# CH32F207_V307V-R3.net
KiCad netlist of a schematic drawn in Altium Designer
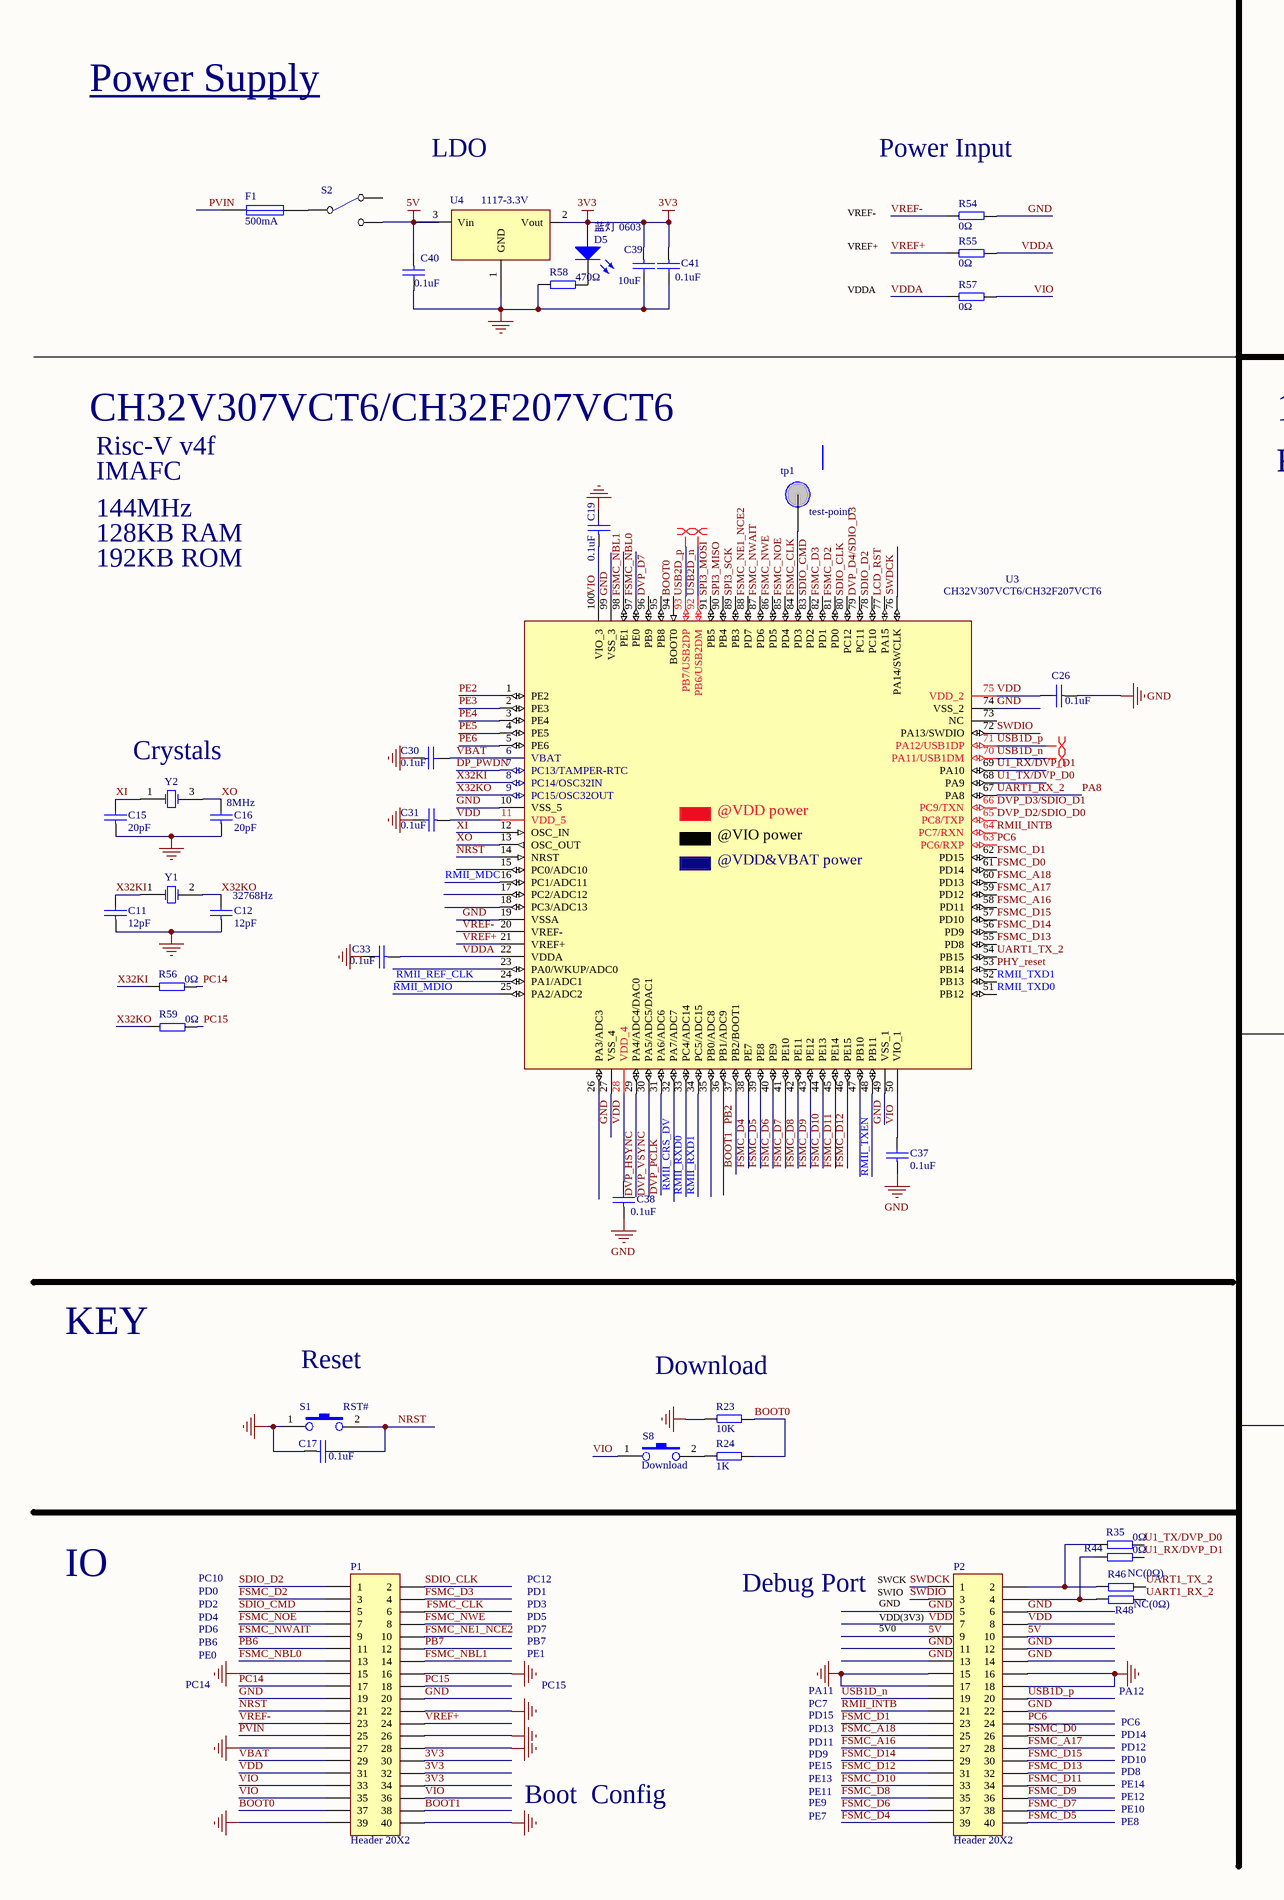
[diagram p0: CH32F207&V307V-R3.SchDoc, left]
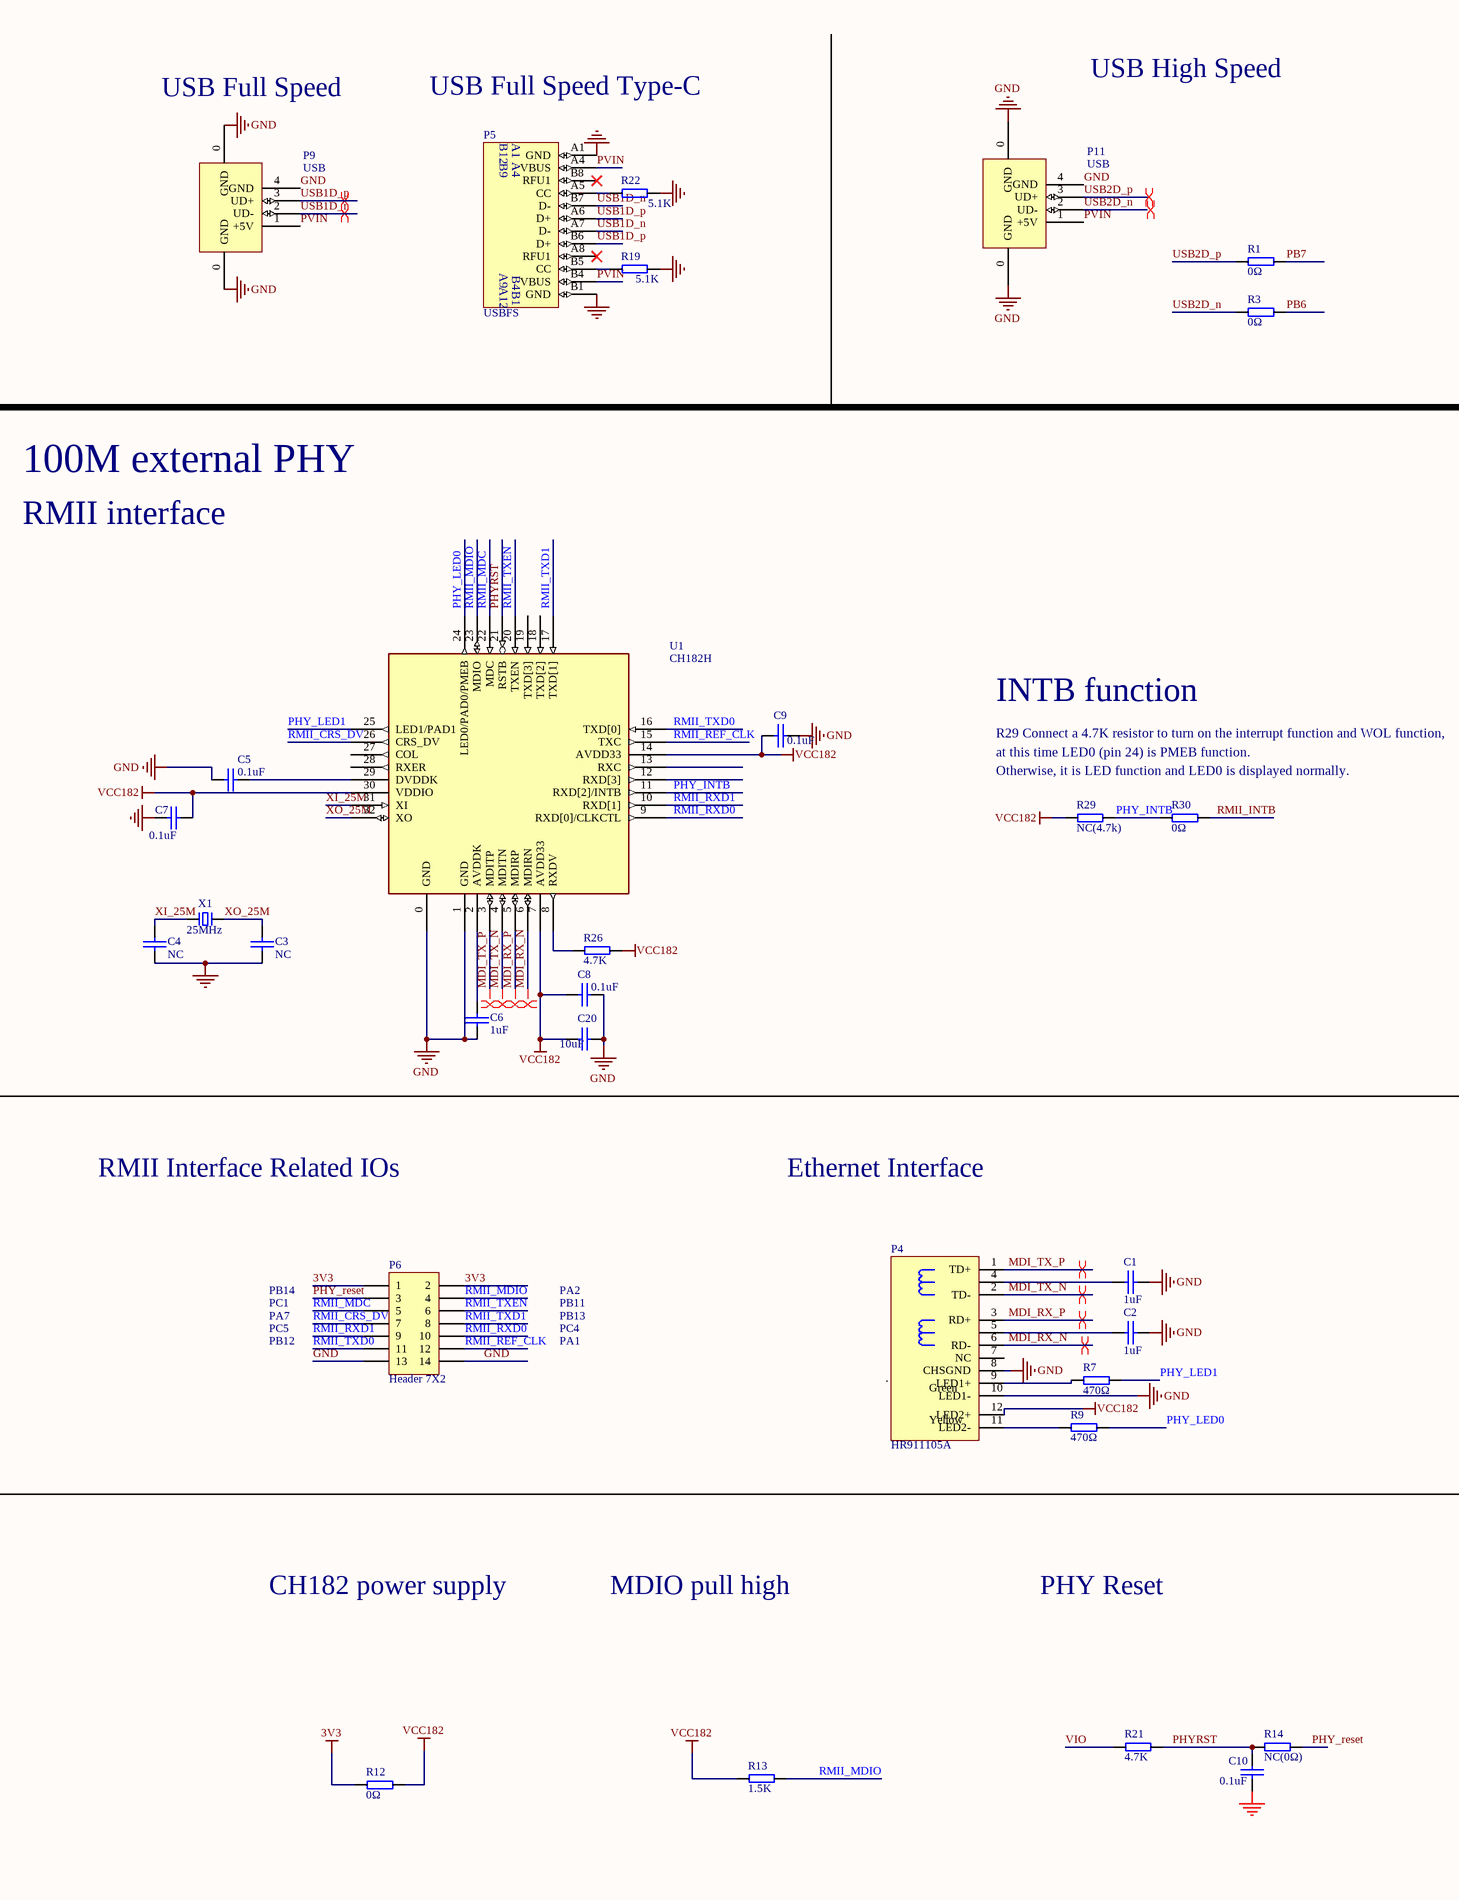
[diagram p1: CH32F207&V307V-R3.SchDoc, right]

(export (version "E")
  (design (tool "Eeschema 10.0.6"))
  (components
    (comp (ref "C1")
      (value "1uF")
      (footprint "0603_C")
      (description "Capacitor")
      (libsource (lib "wch_sch_others") (part "CAP"))
    )
    (comp (ref "C2")
      (value "1uF")
      (footprint "0603_C")
      (description "Capacitor")
      (libsource (lib "wch_sch_others") (part "CAP"))
    )
    (comp (ref "C3")
      (value "NC")
      (footprint "0603_C")
      (description "Capacitor")
      (libsource (lib "wch_sch_others") (part "CAP"))
    )
    (comp (ref "C4")
      (value "NC")
      (footprint "0603_C")
      (description "Capacitor")
      (libsource (lib "wch_sch_others") (part "CAP"))
    )
    (comp (ref "C5")
      (value "0.1uF")
      (footprint "0603_C")
      (description "Capacitor")
      (libsource (lib "wch_sch_others") (part "CAP"))
    )
    (comp (ref "C6")
      (value "1uF")
      (footprint "0603_C")
      (description "Capacitor")
      (libsource (lib "wch_sch_others") (part "CAP"))
    )
    (comp (ref "C7")
      (value "0.1uF")
      (footprint "0603_C")
      (description "Capacitor")
      (libsource (lib "wch_sch_others") (part "CAP"))
    )
    (comp (ref "C8")
      (value "0.1uF")
      (footprint "0603_C")
      (description "Capacitor")
      (libsource (lib "wch_sch_others") (part "CAP"))
    )
    (comp (ref "C9")
      (value "0.1uF")
      (footprint "0603_C")
      (description "Capacitor")
      (libsource (lib "wch_sch_others") (part "CAP"))
    )
    (comp (ref "C10")
      (value "0.1uF")
      (footprint "0603_C")
      (description "Capacitor")
      (libsource (lib "") (part "CAP_1"))
    )
    (comp (ref "C11")
      (value "12pF")
      (footprint "0603_C")
      (description "Capacitor")
      (libsource (lib "") (part "CAP_1"))
    )
    (comp (ref "C12")
      (value "12pF")
      (footprint "0603_C")
      (description "Capacitor")
      (libsource (lib "") (part "CAP_1"))
    )
    (comp (ref "C15")
      (value "20pF")
      (footprint "0603_C")
      (description "Capacitor")
      (libsource (lib "") (part "CAP_1"))
    )
    (comp (ref "C16")
      (value "20pF")
      (footprint "0603_C")
      (description "Capacitor")
      (libsource (lib "") (part "CAP_1"))
    )
    (comp (ref "C17")
      (value "0.1uF")
      (footprint "0603_C")
      (description "Capacitor")
      (libsource (lib "*") (part "CAP"))
    )
    (comp (ref "C19")
      (value "0.1uF")
      (footprint "0603_C")
      (description "Capacitor")
      (libsource (lib "") (part "CAP_1"))
    )
    (comp (ref "C20")
      (value "10uF")
      (footprint "0603_C")
      (description "Capacitor")
      (libsource (lib "wch_sch_others") (part "CAP"))
    )
    (comp (ref "C26")
      (value "0.1uF")
      (footprint "0603_C")
      (description "Capacitor")
      (libsource (lib "") (part "CAP_1"))
    )
    (comp (ref "C30")
      (value "0.1uF")
      (footprint "0603_C")
      (description "Capacitor")
      (libsource (lib "") (part "CAP_1"))
    )
    (comp (ref "C31")
      (value "0.1uF")
      (footprint "0603_C")
      (description "Capacitor")
      (libsource (lib "") (part "CAP_1"))
    )
    (comp (ref "C33")
      (value "0.1uF")
      (footprint "0603_C")
      (description "Capacitor")
      (libsource (lib "") (part "CAP_1"))
    )
    (comp (ref "C37")
      (value "0.1uF")
      (footprint "0603_C")
      (description "Capacitor")
      (libsource (lib "") (part "CAP_1"))
    )
    (comp (ref "C38")
      (value "0.1uF")
      (footprint "0603_C")
      (description "Capacitor")
      (libsource (lib "") (part "CAP_1"))
    )
    (comp (ref "C39")
      (value "10uF")
      (footprint "0603_C")
      (description "Capacitor")
      (libsource (lib "") (part "CAP_1"))
    )
    (comp (ref "C40")
      (value "0.1uF")
      (footprint "0603_C")
      (description "Capacitor")
      (libsource (lib "") (part "CAP_1"))
    )
    (comp (ref "C41")
      (value "0.1uF")
      (footprint "0603_C")
      (description "Capacitor")
      (libsource (lib "") (part "CAP_1"))
    )
    (comp (ref "D5")
      (value "蓝灯 0603")
      (footprint "0603_LED_S1")
      (description "发光二极管")
      (libsource (lib "Miscellaneous Devices LC") (part "0603 蓝灯"))
    )
    (comp (ref "F1")
      (value "500mA")
      (footprint "0805")
      (description "Fuse")
      (fields (field (name "PUBLISHER") "Altium Limited"))
      (libsource (lib "Miscellaneous Devices") (part "Fuse 1"))
    )
    (comp (ref "P1")
      (value "Header 20X2")
      (footprint "HDR2X20")
      (description "Header, 20-Pin, Dual row")
      (fields (field (name "PUBLISHER") "Altium Limited"))
      (libsource (lib "Miscellaneous Connectors") (part "Header 20X2"))
    )
    (comp (ref "P2")
      (value "Header 20X2")
      (footprint "HDR2X20")
      (description "Header, 20-Pin, Dual row")
      (fields (field (name "PUBLISHER") "Altium Limited"))
      (libsource (lib "Miscellaneous Connectors") (part "Header 20X2"))
    )
    (comp (ref "P4")
      (value "HR911105A")
      (footprint "HR911105A")
      (libsource (lib "wch_sch_others") (part "HR911105A_1"))
    )
    (comp (ref "P5")
      (value "USBFS")
      (footprint "TYPE-C-Receptacle-2.0")
      (libsource (lib "*") (part "TYPE-C1"))
    )
    (comp (ref "P6")
      (value "Header 7X2")
      (footprint "IDC14-2.54mm")
      (description "Header, 7-Pin, Dual row")
      (fields (field (name "PUBLISHER") "Altium Limited"))
      (libsource (lib "Miscellaneous Connectors") (part "Header 7X2"))
    )
    (comp (ref "P9")
      (value "USB")
      (footprint "USBAF")
      (description "USB Port")
      (libsource (lib "CHXXX") (part "USB"))
    )
    (comp (ref "P11")
      (value "USB")
      (footprint "USBAF")
      (description "USB Port")
      (libsource (lib "CHXXX") (part "USB"))
    )
    (comp (ref "R1") (value "0Ω") (footprint "0603") (libsource (lib "wch_sch_others") (part "RES")))
    (comp (ref "R3") (value "0Ω") (footprint "0603") (libsource (lib "wch_sch_others") (part "RES")))
    (comp (ref "R7") (value "470Ω") (footprint "0603") (libsource (lib "wch_sch_others") (part "RES")))
    (comp (ref "R9") (value "470Ω") (footprint "0603") (libsource (lib "wch_sch_others") (part "RES")))
    (comp (ref "R12") (value "0Ω") (footprint "0603") (libsource (lib "wch_sch_others") (part "RES")))
    (comp (ref "R13") (value "1.5K") (footprint "0603") (libsource (lib "wch_sch_others") (part "RES")))
    (comp (ref "R14") (value "NC(0Ω)") (footprint "0603") (libsource (lib "wch_sch_others") (part "RES")))
    (comp (ref "R19") (value "5.1K") (footprint "0603") (libsource (lib "wch_sch_others") (part "RES")))
    (comp (ref "R21") (value "4.7K") (footprint "0603") (libsource (lib "wch_sch_others") (part "RES")))
    (comp (ref "R22") (value "5.1K") (footprint "0603") (libsource (lib "wch_sch_others") (part "RES")))
    (comp (ref "R23") (value "10K") (footprint "0603") (libsource (lib "wch_sch_others") (part "RES")))
    (comp (ref "R24") (value "1K") (footprint "0603") (libsource (lib "wch_sch_others") (part "RES")))
    (comp (ref "R26") (value "4.7K") (footprint "0603") (libsource (lib "wch_sch_others") (part "RES")))
    (comp (ref "R29") (value "NC(4.7k)") (footprint "0603") (libsource (lib "wch_sch_others") (part "RES")))
    (comp (ref "R30") (value "0Ω") (footprint "0603") (libsource (lib "wch_sch_others") (part "RES")))
    (comp (ref "R35") (value "0Ω") (footprint "0603") (libsource (lib "wch_sch_others") (part "RES")))
    (comp (ref "R44") (value "0Ω") (footprint "0603") (libsource (lib "wch_sch_others") (part "RES")))
    (comp (ref "R46") (value "NC(0Ω)") (footprint "0603") (libsource (lib "wch_sch_others") (part "RES")))
    (comp (ref "R48") (value "NC(0Ω)") (footprint "0603") (libsource (lib "wch_sch_others") (part "RES")))
    (comp (ref "R54") (value "0Ω") (footprint "0603") (libsource (lib "wch_sch_others") (part "RES")))
    (comp (ref "R55") (value "0Ω") (footprint "0603") (libsource (lib "wch_sch_others") (part "RES")))
    (comp (ref "R56") (value "0Ω") (footprint "0603") (libsource (lib "wch_sch_others") (part "RES")))
    (comp (ref "R57") (value "0Ω") (footprint "0603") (libsource (lib "wch_sch_others") (part "RES")))
    (comp (ref "R58") (value "470Ω") (footprint "0603") (libsource (lib "wch_sch_others") (part "RES")))
    (comp (ref "R59") (value "0Ω") (footprint "0603") (libsource (lib "wch_sch_others") (part "RES")))
    (comp (ref "S1")
      (value "RST#")
      (footprint "SMD_6.1x3.65x2.5mm-KEY")
      (libsource (lib "wch_sch_others") (part "KEY1"))
    )
    (comp (ref "S2")
      (value "SW SPDT")
      (footprint "Horizontal Slide Switch_8.7x4.4mm-2D")
      (libsource (lib "*") (part "SW SPDT"))
    )
    (comp (ref "S8")
      (value "Download")
      (footprint "SMD_6.1x3.65x2.5mm-KEY")
      (libsource (lib "wch_sch_others") (part "KEY1"))
    )
    (comp (ref "tp1")
      (value "test-point")
      (footprint "POINT")
      (description "测试点")
      (libsource (lib "五向开关") (part "test-point"))
    )
    (comp (ref "U1")
      (value "CH182H")
      (footprint "QFN32_5X5")
      (description "MII/RMII 10/100M Ethernet PHY (Transceiver) with auto MDIX")
      (libsource (lib "CHXXX") (part "CH182H"))
    )
    (comp (ref "U3")
      (value "CH32V307VCT6/CH32F207VCT6")
      (footprint "LQFP100")
      (description "RISC-V FPU HD-MCU, 144MHz, USB_480M, USB OTG, 1000M Ethernet MAC, 2*CAN, FSMC+DVP")
      (libsource (lib "CHXXX") (part "CH32V307V"))
    )
    (comp (ref "U4")
      (value "1117-3.3V")
      (footprint "SOT-223")
      (libsource (lib "wch_sch_others") (part "1117-3.3V"))
    )
    (comp (ref "X1")
      (value "25MHz")
      (footprint "SMD-3225_4P")
      (description "2脚无源脚晶振")
      (libsource (lib "10.1 - 保险丝-晶振") (part "XTAL-2P"))
    )
    (comp (ref "Y1")
      (value "32768Hz")
      (footprint "FC-135")
      (description "Crystal Oscillator")
      (fields (field (name "PUBLISHER") "Altium Limited"))
      (libsource (lib "") (part "XTAL_1"))
    )
    (comp (ref "Y2")
      (value "8MHz")
      (footprint "SMD-3225_4P")
      (description "Crystal Oscillator")
      (fields (field (name "PUBLISHER") "Altium Limited"))
      (libsource (lib "*") (part "XTAL"))
    )
  )
  (nets
    (net (code "2") (name "/BOOT0") (class "Default")
      (node (ref "P1") (pin "37") (pinfunction "37_37") (pintype "passive"))
      (node (ref "R23") (pin "1") (pintype "passive"))
      (node (ref "R24") (pin "1") (pintype "passive"))
      (node (ref "U3") (pin "94") (pinfunction "BOOT0_94") (pintype "input"))
    )
    (net (code "3") (name "/BOOT1") (class "Default")
      (node (ref "P1") (pin "38") (pinfunction "38_38") (pintype "passive"))
      (node (ref "U3") (pin "37") (pinfunction "PB2/BOOT1_37") (pintype "bidirectional"))
    )
    (net (code "4") (name "/DP_PWDN") (class "Default")
      (node (ref "U3") (pin "7") (pinfunction "PC13/TAMPER-RTC_7") (pintype "bidirectional"))
    )
    (net (code "5") (name "/DVP_D2{slash}SDIO_D0") (class "Default")
      (node (ref "U3") (pin "65") (pinfunction "PC8/TXP_65") (pintype "bidirectional"))
    )
    (net (code "6") (name "/DVP_D3{slash}SDIO_D1") (class "Default")
      (node (ref "U3") (pin "66") (pinfunction "PC9/TXN_66") (pintype "bidirectional"))
    )
    (net (code "7") (name "/DVP_D4{slash}SDIO_D3") (class "Default")
      (node (ref "U3") (pin "79") (pinfunction "PC11_79") (pintype "bidirectional"))
    )
    (net (code "8") (name "/DVP_D7") (class "Default")
      (node (ref "U3") (pin "96") (pinfunction "PB9_96") (pintype "bidirectional"))
    )
    (net (code "9") (name "/DVP_HSYNC") (class "Default")
      (node (ref "U3") (pin "29") (pinfunction "PA4/ADC4/DAC0_29") (pintype "bidirectional"))
    )
    (net (code "10") (name "/DVP_PCLK") (class "Default")
      (node (ref "U3") (pin "31") (pinfunction "PA6/ADC6_31") (pintype "bidirectional"))
    )
    (net (code "11") (name "/DVP_VSYNC") (class "Default")
      (node (ref "U3") (pin "30") (pinfunction "PA5/ADC5/DAC1_30") (pintype "bidirectional"))
    )
    (net (code "12") (name "/FSMC_A16") (class "Default")
      (node (ref "P2") (pin "27") (pinfunction "27_27") (pintype "passive"))
      (node (ref "U3") (pin "58") (pinfunction "PD11_58") (pintype "bidirectional"))
    )
    (net (code "13") (name "/FSMC_A17") (class "Default")
      (node (ref "P2") (pin "28") (pinfunction "28_28") (pintype "passive"))
      (node (ref "U3") (pin "59") (pinfunction "PD12_59") (pintype "bidirectional"))
    )
    (net (code "14") (name "/FSMC_A18") (class "Default")
      (node (ref "P2") (pin "25") (pinfunction "25_25") (pintype "passive"))
      (node (ref "U3") (pin "60") (pinfunction "PD13_60") (pintype "bidirectional"))
    )
    (net (code "15") (name "/FSMC_CLK") (class "Default")
      (node (ref "P1") (pin "6") (pinfunction "6_6") (pintype "passive"))
      (node (ref "U3") (pin "84") (pinfunction "PD3_84") (pintype "bidirectional"))
      (node (ref "tp1") (pin "1") (pinfunction "point_1") (pintype "passive"))
    )
    (net (code "16") (name "/FSMC_D0") (class "Default")
      (node (ref "P2") (pin "26") (pinfunction "26_26") (pintype "passive"))
      (node (ref "U3") (pin "61") (pinfunction "PD14_61") (pintype "bidirectional"))
    )
    (net (code "17") (name "/FSMC_D1") (class "Default")
      (node (ref "P2") (pin "23") (pinfunction "23_23") (pintype "passive"))
      (node (ref "U3") (pin "62") (pinfunction "PD15_62") (pintype "bidirectional"))
    )
    (net (code "18") (name "/FSMC_D2") (class "Default")
      (node (ref "P1") (pin "3") (pinfunction "3_3") (pintype "passive"))
      (node (ref "U3") (pin "81") (pinfunction "PD0_81") (pintype "bidirectional"))
    )
    (net (code "19") (name "/FSMC_D3") (class "Default")
      (node (ref "P1") (pin "4") (pinfunction "4_4") (pintype "passive"))
      (node (ref "U3") (pin "82") (pinfunction "PD1_82") (pintype "bidirectional"))
    )
    (net (code "20") (name "/FSMC_D4") (class "Default")
      (node (ref "P2") (pin "39") (pinfunction "39_39") (pintype "passive"))
      (node (ref "U3") (pin "38") (pinfunction "PE7_38") (pintype "bidirectional"))
    )
    (net (code "21") (name "/FSMC_D5") (class "Default")
      (node (ref "P2") (pin "40") (pinfunction "40_40") (pintype "passive"))
      (node (ref "U3") (pin "39") (pinfunction "PE8_39") (pintype "bidirectional"))
    )
    (net (code "22") (name "/FSMC_D6") (class "Default")
      (node (ref "P2") (pin "37") (pinfunction "37_37") (pintype "passive"))
      (node (ref "U3") (pin "40") (pinfunction "PE9_40") (pintype "bidirectional"))
    )
    (net (code "23") (name "/FSMC_D7") (class "Default")
      (node (ref "P2") (pin "38") (pinfunction "38_38") (pintype "passive"))
      (node (ref "U3") (pin "41") (pinfunction "PE10_41") (pintype "bidirectional"))
    )
    (net (code "24") (name "/FSMC_D8") (class "Default")
      (node (ref "P2") (pin "35") (pinfunction "35_35") (pintype "passive"))
      (node (ref "U3") (pin "42") (pinfunction "PE11_42") (pintype "bidirectional"))
    )
    (net (code "25") (name "/FSMC_D9") (class "Default")
      (node (ref "P2") (pin "36") (pinfunction "36_36") (pintype "passive"))
      (node (ref "U3") (pin "43") (pinfunction "PE12_43") (pintype "bidirectional"))
    )
    (net (code "26") (name "/FSMC_D10") (class "Default")
      (node (ref "P2") (pin "33") (pinfunction "33_33") (pintype "passive"))
      (node (ref "U3") (pin "44") (pinfunction "PE13_44") (pintype "bidirectional"))
    )
    (net (code "27") (name "/FSMC_D11") (class "Default")
      (node (ref "P2") (pin "34") (pinfunction "34_34") (pintype "passive"))
      (node (ref "U3") (pin "45") (pinfunction "PE14_45") (pintype "bidirectional"))
    )
    (net (code "28") (name "/FSMC_D12") (class "Default")
      (node (ref "P2") (pin "31") (pinfunction "31_31") (pintype "passive"))
      (node (ref "U3") (pin "46") (pinfunction "PE15_46") (pintype "bidirectional"))
    )
    (net (code "29") (name "/FSMC_D13") (class "Default")
      (node (ref "P2") (pin "32") (pinfunction "32_32") (pintype "passive"))
      (node (ref "U3") (pin "55") (pinfunction "PD8_55") (pintype "bidirectional"))
    )
    (net (code "30") (name "/FSMC_D14") (class "Default")
      (node (ref "P2") (pin "29") (pinfunction "29_29") (pintype "passive"))
      (node (ref "U3") (pin "56") (pinfunction "PD9_56") (pintype "bidirectional"))
    )
    (net (code "31") (name "/FSMC_D15") (class "Default")
      (node (ref "P2") (pin "30") (pinfunction "30_30") (pintype "passive"))
      (node (ref "U3") (pin "57") (pinfunction "PD10_57") (pintype "bidirectional"))
    )
    (net (code "32") (name "/FSMC_NBL0") (class "Default")
      (node (ref "P1") (pin "13") (pinfunction "13_13") (pintype "passive"))
      (node (ref "U3") (pin "97") (pinfunction "PE0_97") (pintype "bidirectional"))
    )
    (net (code "33") (name "/FSMC_NBL1") (class "Default")
      (node (ref "P1") (pin "14") (pinfunction "14_14") (pintype "passive"))
      (node (ref "U3") (pin "98") (pinfunction "PE1_98") (pintype "bidirectional"))
    )
    (net (code "34") (name "/FSMC_NE1_NCE2") (class "Default")
      (node (ref "P1") (pin "10") (pinfunction "10_10") (pintype "passive"))
      (node (ref "U3") (pin "88") (pinfunction "PD7_88") (pintype "bidirectional"))
    )
    (net (code "35") (name "/FSMC_NOE") (class "Default")
      (node (ref "P1") (pin "7") (pinfunction "7_7") (pintype "passive"))
      (node (ref "U3") (pin "85") (pinfunction "PD4_85") (pintype "bidirectional"))
    )
    (net (code "36") (name "/FSMC_NWAIT") (class "Default")
      (node (ref "P1") (pin "9") (pinfunction "9_9") (pintype "passive"))
      (node (ref "U3") (pin "87") (pinfunction "PD6_87") (pintype "bidirectional"))
    )
    (net (code "37") (name "/FSMC_NWE") (class "Default")
      (node (ref "P1") (pin "8") (pinfunction "8_8") (pintype "passive"))
      (node (ref "U3") (pin "86") (pinfunction "PD5_86") (pintype "bidirectional"))
    )
    (net (code "38") (name "/LCD_RST") (class "Default")
      (node (ref "U3") (pin "77") (pinfunction "PA15_77") (pintype "bidirectional"))
    )
    (net (code "39") (name "/MDI_RX_N") (class "Default")
      (node (ref "P4") (pin "6") (pinfunction "RD-_6") (pintype "passive"))
      (node (ref "U1") (pin "6") (pinfunction "MDIRN_6") (pintype "bidirectional"))
    )
    (net (code "40") (name "/MDI_RX_P") (class "Default")
      (node (ref "P4") (pin "3") (pinfunction "RD+_3") (pintype "passive"))
      (node (ref "U1") (pin "5") (pinfunction "MDIRP_5") (pintype "bidirectional"))
    )
    (net (code "41") (name "/MDI_TX_N") (class "Default")
      (node (ref "P4") (pin "2") (pinfunction "TD-_2") (pintype "passive"))
      (node (ref "U1") (pin "4") (pinfunction "MDITN_4") (pintype "bidirectional"))
    )
    (net (code "42") (name "/MDI_TX_P") (class "Default")
      (node (ref "P4") (pin "1") (pinfunction "TD+_1") (pintype "passive"))
      (node (ref "U1") (pin "3") (pinfunction "MDITP_3") (pintype "bidirectional"))
    )
    (net (code "43") (name "/NRST") (class "Default")
      (node (ref "C17") (pin "2") (pinfunction "2_2") (pintype "passive"))
      (node (ref "P1") (pin "21") (pinfunction "21_21") (pintype "passive"))
      (node (ref "S1") (pin "2") (pinfunction "2_2") (pintype "passive"))
      (node (ref "U3") (pin "14") (pinfunction "NRST_14") (pintype "input"))
    )
    (net (code "44") (name "/PA8") (class "Default")
      (node (ref "R48") (pin "2") (pintype "passive"))
      (node (ref "U3") (pin "67") (pinfunction "PA8_67") (pintype "bidirectional"))
    )
    (net (code "45") (name "/PB6") (class "Default")
      (node (ref "P1") (pin "11") (pinfunction "11_11") (pintype "passive"))
      (node (ref "R3") (pin "2") (pintype "passive"))
    )
    (net (code "46") (name "/PB7") (class "Default")
      (node (ref "P1") (pin "12") (pinfunction "12_12") (pintype "passive"))
      (node (ref "R1") (pin "2") (pintype "passive"))
    )
    (net (code "47") (name "/PC6") (class "Default")
      (node (ref "P2") (pin "24") (pinfunction "24_24") (pintype "passive"))
      (node (ref "U3") (pin "63") (pinfunction "PC6/RXP_63") (pintype "bidirectional"))
    )
    (net (code "48") (name "/PC14") (class "Default")
      (node (ref "P1") (pin "17") (pinfunction "17_17") (pintype "passive"))
      (node (ref "R56") (pin "2") (pintype "passive"))
    )
    (net (code "49") (name "/PC15") (class "Default")
      (node (ref "P1") (pin "18") (pinfunction "18_18") (pintype "passive"))
      (node (ref "R59") (pin "2") (pintype "passive"))
    )
    (net (code "50") (name "/PE2") (class "Default")
      (node (ref "U3") (pin "1") (pinfunction "PE2_1") (pintype "bidirectional"))
    )
    (net (code "51") (name "/PE3") (class "Default")
      (node (ref "U3") (pin "2") (pinfunction "PE3_2") (pintype "bidirectional"))
    )
    (net (code "52") (name "/PE4") (class "Default")
      (node (ref "U3") (pin "3") (pinfunction "PE4_3") (pintype "bidirectional"))
    )
    (net (code "53") (name "/PE5") (class "Default")
      (node (ref "U3") (pin "4") (pinfunction "PE5_4") (pintype "bidirectional"))
    )
    (net (code "54") (name "/PE6") (class "Default")
      (node (ref "U3") (pin "5") (pinfunction "PE6_5") (pintype "bidirectional"))
    )
    (net (code "55") (name "/PHYRST") (class "Default")
      (node (ref "C10") (pin "2") (pinfunction "2_2") (pintype "passive"))
      (node (ref "R14") (pin "1") (pintype "passive"))
      (node (ref "R21") (pin "1") (pintype "passive"))
      (node (ref "U1") (pin "21") (pinfunction "RSTB_21") (pintype "input"))
    )
    (net (code "56") (name "/PHY_INTB") (class "Default")
      (node (ref "R29") (pin "1") (pintype "passive"))
      (node (ref "R30") (pin "1") (pintype "passive"))
      (node (ref "U1") (pin "11") (pinfunction "RXD[2]/INTB_11") (pintype "output"))
    )
    (net (code "57") (name "/PHY_LED0") (class "Default")
      (node (ref "R9") (pin "2") (pintype "passive"))
      (node (ref "U1") (pin "24") (pinfunction "LED0/PAD0/PMEB_24") (pintype "output"))
    )
    (net (code "58") (name "/PHY_LED1") (class "Default")
      (node (ref "R7") (pin "2") (pintype "passive"))
      (node (ref "U1") (pin "25") (pinfunction "LED1/PAD1_25") (pintype "output"))
    )
    (net (code "59") (name "/PHY_reset") (class "Default")
      (node (ref "P6") (pin "3") (pinfunction "3_3") (pintype "passive"))
      (node (ref "R14") (pin "2") (pintype "passive"))
      (node (ref "U3") (pin "53") (pinfunction "PB14_53") (pintype "bidirectional"))
    )
    (net (code "60") (name "/PVIN") (class "Default")
      (node (ref "F1") (pin "1") (pinfunction "1_1") (pintype "passive"))
      (node (ref "P1") (pin "25") (pinfunction "25_25") (pintype "passive"))
      (node (ref "P11") (pin "1") (pinfunction "+5V_1") (pintype "power_in"))
      (node (ref "P5") (pin "A4") (pinfunction "VBUS_A4") (pintype "bidirectional"))
      (node (ref "P5") (pin "B4") (pinfunction "VBUS_B4") (pintype "bidirectional"))
      (node (ref "P9") (pin "1") (pinfunction "+5V_1") (pintype "power_in"))
    )
    (net (code "61") (name "/RMII_CRS_DV") (class "Default")
      (node (ref "P6") (pin "7") (pinfunction "7_7") (pintype "passive"))
      (node (ref "U1") (pin "26") (pinfunction "CRS_DV_26") (pintype "output"))
      (node (ref "U3") (pin "32") (pinfunction "PA7/ADC7_32") (pintype "bidirectional"))
    )
    (net (code "62") (name "/RMII_INTB") (class "Default")
      (node (ref "P2") (pin "21") (pinfunction "21_21") (pintype "passive"))
      (node (ref "R30") (pin "2") (pintype "passive"))
      (node (ref "U3") (pin "64") (pinfunction "PC7/RXN_64") (pintype "bidirectional"))
    )
    (net (code "63") (name "/RMII_MDC") (class "Default")
      (node (ref "P6") (pin "5") (pinfunction "5_5") (pintype "passive"))
      (node (ref "U1") (pin "22") (pinfunction "MDC_22") (pintype "input"))
      (node (ref "U3") (pin "16") (pinfunction "PC1/ADC11_16") (pintype "bidirectional"))
    )
    (net (code "64") (name "/RMII_MDIO") (class "Default")
      (node (ref "P6") (pin "4") (pinfunction "4_4") (pintype "passive"))
      (node (ref "R13") (pin "2") (pintype "passive"))
      (node (ref "U1") (pin "23") (pinfunction "MDIO_23") (pintype "bidirectional"))
      (node (ref "U3") (pin "25") (pinfunction "PA2/ADC2_25") (pintype "bidirectional"))
    )
    (net (code "65") (name "/RMII_REF_CLK") (class "Default")
      (node (ref "P6") (pin "12") (pinfunction "12_12") (pintype "passive"))
      (node (ref "U1") (pin "15") (pinfunction "TXC_15") (pintype "output"))
      (node (ref "U3") (pin "24") (pinfunction "PA1/ADC1_24") (pintype "bidirectional"))
    )
    (net (code "66") (name "/RMII_RXD0") (class "Default")
      (node (ref "P6") (pin "10") (pinfunction "10_10") (pintype "passive"))
      (node (ref "U1") (pin "9") (pinfunction "RXD[0]/CLKCTL_9") (pintype "output"))
      (node (ref "U3") (pin "33") (pinfunction "PC4/ADC14_33") (pintype "bidirectional"))
    )
    (net (code "67") (name "/RMII_RXD1") (class "Default")
      (node (ref "P6") (pin "9") (pinfunction "9_9") (pintype "passive"))
      (node (ref "U1") (pin "10") (pinfunction "RXD[1]_10") (pintype "output"))
      (node (ref "U3") (pin "34") (pinfunction "PC5/ADC15_34") (pintype "bidirectional"))
    )
    (net (code "68") (name "/RMII_TXD0") (class "Default")
      (node (ref "P6") (pin "11") (pinfunction "11_11") (pintype "passive"))
      (node (ref "U1") (pin "16") (pinfunction "TXD[0]_16") (pintype "input"))
      (node (ref "U3") (pin "51") (pinfunction "PB12_51") (pintype "bidirectional"))
    )
    (net (code "69") (name "/RMII_TXD1") (class "Default")
      (node (ref "P6") (pin "8") (pinfunction "8_8") (pintype "passive"))
      (node (ref "U1") (pin "17") (pinfunction "TXD[1]_17") (pintype "input"))
      (node (ref "U3") (pin "52") (pinfunction "PB13_52") (pintype "bidirectional"))
    )
    (net (code "70") (name "/RMII_TXEN") (class "Default")
      (node (ref "P6") (pin "6") (pinfunction "6_6") (pintype "passive"))
      (node (ref "U1") (pin "20") (pinfunction "TXEN_20") (pintype "input"))
      (node (ref "U3") (pin "48") (pinfunction "PB11_48") (pintype "bidirectional"))
    )
    (net (code "71") (name "/SDIO_CLK") (class "Default")
      (node (ref "P1") (pin "2") (pinfunction "2_2") (pintype "passive"))
      (node (ref "U3") (pin "80") (pinfunction "PC12_80") (pintype "bidirectional"))
    )
    (net (code "72") (name "/SDIO_CMD") (class "Default")
      (node (ref "P1") (pin "5") (pinfunction "5_5") (pintype "passive"))
      (node (ref "U3") (pin "83") (pinfunction "PD2_83") (pintype "bidirectional"))
    )
    (net (code "73") (name "/SDIO_D2") (class "Default")
      (node (ref "P1") (pin "1") (pinfunction "1_1") (pintype "passive"))
      (node (ref "U3") (pin "78") (pinfunction "PC10_78") (pintype "bidirectional"))
    )
    (net (code "74") (name "/SPI3_MISO") (class "Default")
      (node (ref "U3") (pin "90") (pinfunction "PB4_90") (pintype "bidirectional"))
    )
    (net (code "75") (name "/SPI3_MOSI") (class "Default")
      (node (ref "U3") (pin "91") (pinfunction "PB5_91") (pintype "bidirectional"))
    )
    (net (code "76") (name "/SPI3_SCK") (class "Default")
      (node (ref "U3") (pin "89") (pinfunction "PB3_89") (pintype "bidirectional"))
    )
    (net (code "77") (name "/SWDCK") (class "Default")
      (node (ref "P2") (pin "1") (pinfunction "1_1") (pintype "passive"))
      (node (ref "U3") (pin "76") (pinfunction "PA14/SWCLK_76") (pintype "bidirectional"))
    )
    (net (code "78") (name "/SWDIO") (class "Default")
      (node (ref "P2") (pin "3") (pinfunction "3_3") (pintype "passive"))
      (node (ref "U3") (pin "72") (pinfunction "PA13/SWDIO_72") (pintype "bidirectional"))
    )
    (net (code "79") (name "/U1_RX{slash}DVP_D1") (class "Default")
      (node (ref "R44") (pin "2") (pintype "passive"))
      (node (ref "U3") (pin "69") (pinfunction "PA10_69") (pintype "bidirectional"))
    )
    (net (code "80") (name "/U1_TX{slash}DVP_D0") (class "Default")
      (node (ref "R35") (pin "2") (pintype "passive"))
      (node (ref "U3") (pin "68") (pinfunction "PA9_68") (pintype "bidirectional"))
    )
    (net (code "81") (name "/UART1_TX_2") (class "Default")
      (node (ref "R46") (pin "2") (pintype "passive"))
      (node (ref "U3") (pin "54") (pinfunction "PB15_54") (pintype "bidirectional"))
    )
    (net (code "82") (name "/USB1D_n") (class "Default")
      (node (ref "P2") (pin "19") (pinfunction "19_19") (pintype "passive"))
      (node (ref "P5") (pin "A7") (pinfunction "D-_A7") (pintype "bidirectional"))
      (node (ref "P5") (pin "B7") (pinfunction "D-_B7") (pintype "bidirectional"))
      (node (ref "P9") (pin "2") (pinfunction "UD-_2") (pintype "bidirectional"))
      (node (ref "U3") (pin "70") (pinfunction "PA11/USB1DM_70") (pintype "bidirectional"))
    )
    (net (code "83") (name "/USB1D_p") (class "Default")
      (node (ref "P2") (pin "20") (pinfunction "20_20") (pintype "passive"))
      (node (ref "P5") (pin "A6") (pinfunction "D+_A6") (pintype "bidirectional"))
      (node (ref "P5") (pin "B6") (pinfunction "D+_B6") (pintype "bidirectional"))
      (node (ref "P9") (pin "3") (pinfunction "UD+_3") (pintype "bidirectional"))
      (node (ref "U3") (pin "71") (pinfunction "PA12/USB1DP_71") (pintype "bidirectional"))
    )
    (net (code "84") (name "/USB2D_n") (class "Default")
      (node (ref "P11") (pin "2") (pinfunction "UD-_2") (pintype "bidirectional"))
      (node (ref "R3") (pin "1") (pintype "passive"))
      (node (ref "U3") (pin "92") (pinfunction "PB6/USB2DM_92") (pintype "bidirectional"))
    )
    (net (code "85") (name "/USB2D_p") (class "Default")
      (node (ref "P11") (pin "3") (pinfunction "UD+_3") (pintype "bidirectional"))
      (node (ref "R1") (pin "1") (pintype "passive"))
      (node (ref "U3") (pin "93") (pinfunction "PB7/USB2DP_93") (pintype "bidirectional"))
    )
    (net (code "86") (name "/VBAT") (class "Default")
      (node (ref "C30") (pin "2") (pinfunction "2_2") (pintype "passive"))
      (node (ref "P1") (pin "29") (pinfunction "29_29") (pintype "passive"))
      (node (ref "U3") (pin "6") (pinfunction "VBAT_6") (pintype "power_in"))
    )
    (net (code "87") (name "/VDD") (class "Default")
      (node (ref "C26") (pin "2") (pinfunction "2_2") (pintype "passive"))
      (node (ref "C31") (pin "1") (pinfunction "1_1") (pintype "passive"))
      (node (ref "C38") (pin "2") (pinfunction "2_2") (pintype "passive"))
      (node (ref "P1") (pin "31") (pinfunction "31_31") (pintype "passive"))
      (node (ref "P2") (pin "7") (pinfunction "7_7") (pintype "passive"))
      (node (ref "P2") (pin "8") (pinfunction "8_8") (pintype "passive"))
      (node (ref "U3") (pin "11") (pinfunction "VDD_5_11") (pintype "power_in"))
      (node (ref "U3") (pin "28") (pinfunction "VDD_4_28") (pintype "power_in"))
      (node (ref "U3") (pin "75") (pinfunction "VDD_2_75") (pintype "power_in"))
    )
    (net (code "88") (name "/VDDA") (class "Default")
      (node (ref "C33") (pin "1") (pinfunction "1_1") (pintype "passive"))
      (node (ref "R55") (pin "1") (pintype "passive"))
      (node (ref "R57") (pin "2") (pintype "passive"))
      (node (ref "U3") (pin "22") (pinfunction "VDDA_22") (pintype "power_in"))
    )
    (net (code "89") (name "/VIO") (class "Default")
      (node (ref "C19") (pin "1") (pinfunction "1_1") (pintype "passive"))
      (node (ref "C37") (pin "2") (pinfunction "2_2") (pintype "passive"))
      (node (ref "P1") (pin "33") (pinfunction "33_33") (pintype "passive"))
      (node (ref "P1") (pin "35") (pinfunction "35_35") (pintype "passive"))
      (node (ref "P1") (pin "36") (pinfunction "36_36") (pintype "passive"))
      (node (ref "R21") (pin "2") (pintype "passive"))
      (node (ref "R57") (pin "1") (pintype "passive"))
      (node (ref "S8") (pin "1") (pinfunction "1_1") (pintype "passive"))
      (node (ref "U3") (pin "100") (pinfunction "VIO_3_100") (pintype "power_in"))
      (node (ref "U3") (pin "50") (pinfunction "VIO_1_50") (pintype "power_in"))
    )
    (net (code "90") (name "/VREF+") (class "Default")
      (node (ref "P1") (pin "24") (pinfunction "24_24") (pintype "passive"))
      (node (ref "R55") (pin "2") (pintype "passive"))
      (node (ref "U3") (pin "21") (pinfunction "VREF+_21") (pintype "power_in"))
    )
    (net (code "91") (name "/VREF-") (class "Default")
      (node (ref "P1") (pin "23") (pinfunction "23_23") (pintype "passive"))
      (node (ref "R54") (pin "2") (pintype "passive"))
      (node (ref "U3") (pin "20") (pinfunction "VREF-_20") (pintype "power_in"))
    )
    (net (code "92") (name "/X32KI") (class "Default")
      (node (ref "C11") (pin "2") (pinfunction "2_2") (pintype "passive"))
      (node (ref "R56") (pin "1") (pintype "passive"))
      (node (ref "U3") (pin "8") (pinfunction "PC14/OSC32IN_8") (pintype "bidirectional"))
      (node (ref "Y1") (pin "1") (pinfunction "OSC1_1") (pintype "passive"))
    )
    (net (code "93") (name "/X32KO") (class "Default")
      (node (ref "C12") (pin "2") (pinfunction "2_2") (pintype "passive"))
      (node (ref "R59") (pin "1") (pintype "passive"))
      (node (ref "U3") (pin "9") (pinfunction "PC15/OSC32OUT_9") (pintype "bidirectional"))
      (node (ref "Y1") (pin "2") (pinfunction "OSC2_2") (pintype "passive"))
    )
    (net (code "94") (name "/XI") (class "Default")
      (node (ref "C15") (pin "2") (pinfunction "2_2") (pintype "passive"))
      (node (ref "U3") (pin "12") (pinfunction "OSC_IN_12") (pintype "input"))
      (node (ref "Y2") (pin "1") (pinfunction "OSC1_1") (pintype "passive"))
    )
    (net (code "95") (name "/XI_25M") (class "Default")
      (node (ref "C4") (pin "2") (pinfunction "2_2") (pintype "passive"))
      (node (ref "U1") (pin "31") (pinfunction "XI_31") (pintype "input"))
      (node (ref "X1") (pin "1") (pinfunction "1_1") (pintype "passive"))
    )
    (net (code "96") (name "/XO") (class "Default")
      (node (ref "C16") (pin "2") (pinfunction "2_2") (pintype "passive"))
      (node (ref "U3") (pin "13") (pinfunction "OSC_OUT_13") (pintype "output"))
      (node (ref "Y2") (pin "3") (pinfunction "OSC2_3") (pintype "passive"))
    )
    (net (code "97") (name "/XO_25M") (class "Default")
      (node (ref "C3") (pin "2") (pinfunction "2_2") (pintype "passive"))
      (node (ref "U1") (pin "32") (pinfunction "XO_32") (pintype "bidirectional"))
      (node (ref "X1") (pin "3") (pinfunction "2_3") (pintype "passive"))
    )
    (net (code "98") (name "3V3") (class "Default")
      (node (ref "C39") (pin "1") (pinfunction "1_1") (pintype "passive"))
      (node (ref "C41") (pin "1") (pinfunction "1_1") (pintype "passive"))
      (node (ref "D5") (pin "A") (pinfunction "A_A") (pintype "passive"))
      (node (ref "P1") (pin "30") (pinfunction "30_30") (pintype "passive"))
      (node (ref "P1") (pin "32") (pinfunction "32_32") (pintype "passive"))
      (node (ref "P1") (pin "34") (pinfunction "34_34") (pintype "passive"))
      (node (ref "P6") (pin "1") (pinfunction "1_1") (pintype "passive"))
      (node (ref "P6") (pin "2") (pinfunction "2_2") (pintype "passive"))
      (node (ref "R12") (pin "2") (pintype "passive"))
      (node (ref "U4") (pin "2") (pinfunction "Vout_2") (pintype "passive"))
    )
    (net (code "99") (name "5V") (class "Default")
      (node (ref "C40") (pin "1") (pinfunction "1_1") (pintype "passive"))
      (node (ref "P2") (pin "10") (pinfunction "10_10") (pintype "passive"))
      (node (ref "P2") (pin "9") (pinfunction "9_9") (pintype "passive"))
      (node (ref "S2") (pin "2") (pinfunction "NC_2") (pintype "passive"))
      (node (ref "U4") (pin "3") (pinfunction "Vin_3") (pintype "passive"))
    )
    (net (code "100") (name "GND") (class "Default")
      (node (ref "C1") (pin "1") (pinfunction "1_1") (pintype "passive"))
      (node (ref "C10") (pin "1") (pinfunction "1_1") (pintype "passive"))
      (node (ref "C11") (pin "1") (pinfunction "1_1") (pintype "passive"))
      (node (ref "C12") (pin "1") (pinfunction "1_1") (pintype "passive"))
      (node (ref "C15") (pin "1") (pinfunction "1_1") (pintype "passive"))
      (node (ref "C16") (pin "1") (pinfunction "1_1") (pintype "passive"))
      (node (ref "C17") (pin "1") (pinfunction "1_1") (pintype "passive"))
      (node (ref "C19") (pin "2") (pinfunction "2_2") (pintype "passive"))
      (node (ref "C2") (pin "1") (pinfunction "1_1") (pintype "passive"))
      (node (ref "C20") (pin "1") (pinfunction "1_1") (pintype "passive"))
      (node (ref "C26") (pin "1") (pinfunction "1_1") (pintype "passive"))
      (node (ref "C3") (pin "1") (pinfunction "1_1") (pintype "passive"))
      (node (ref "C30") (pin "1") (pinfunction "1_1") (pintype "passive"))
      (node (ref "C31") (pin "2") (pinfunction "2_2") (pintype "passive"))
      (node (ref "C33") (pin "2") (pinfunction "2_2") (pintype "passive"))
      (node (ref "C37") (pin "1") (pinfunction "1_1") (pintype "passive"))
      (node (ref "C38") (pin "1") (pinfunction "1_1") (pintype "passive"))
      (node (ref "C39") (pin "2") (pinfunction "2_2") (pintype "passive"))
      (node (ref "C4") (pin "1") (pinfunction "1_1") (pintype "passive"))
      (node (ref "C40") (pin "2") (pinfunction "2_2") (pintype "passive"))
      (node (ref "C41") (pin "2") (pinfunction "2_2") (pintype "passive"))
      (node (ref "C5") (pin "1") (pinfunction "1_1") (pintype "passive"))
      (node (ref "C6") (pin "1") (pinfunction "1_1") (pintype "passive"))
      (node (ref "C7") (pin "1") (pinfunction "1_1") (pintype "passive"))
      (node (ref "C8") (pin "1") (pinfunction "1_1") (pintype "passive"))
      (node (ref "C9") (pin "1") (pinfunction "1_1") (pintype "passive"))
      (node (ref "P1") (pin "15") (pinfunction "15_15") (pintype "passive"))
      (node (ref "P1") (pin "16") (pinfunction "16_16") (pintype "passive"))
      (node (ref "P1") (pin "19") (pinfunction "19_19") (pintype "passive"))
      (node (ref "P1") (pin "20") (pinfunction "20_20") (pintype "passive"))
      (node (ref "P1") (pin "22") (pinfunction "22_22") (pintype "passive"))
      (node (ref "P1") (pin "26") (pinfunction "26_26") (pintype "passive"))
      (node (ref "P1") (pin "27") (pinfunction "27_27") (pintype "passive"))
      (node (ref "P1") (pin "28") (pinfunction "28_28") (pintype "passive"))
      (node (ref "P1") (pin "39") (pinfunction "39_39") (pintype "passive"))
      (node (ref "P1") (pin "40") (pinfunction "40_40") (pintype "passive"))
      (node (ref "P11") (pin "0") (pinfunction "GND_0") (pintype "power_in"))
      (node (ref "P11") (pin "4") (pinfunction "GND_4") (pintype "power_in"))
      (node (ref "P2") (pin "11") (pinfunction "11_11") (pintype "passive"))
      (node (ref "P2") (pin "12") (pinfunction "12_12") (pintype "passive"))
      (node (ref "P2") (pin "13") (pinfunction "13_13") (pintype "passive"))
      (node (ref "P2") (pin "14") (pinfunction "14_14") (pintype "passive"))
      (node (ref "P2") (pin "15") (pinfunction "15_15") (pintype "passive"))
      (node (ref "P2") (pin "16") (pinfunction "16_16") (pintype "passive"))
      (node (ref "P2") (pin "17") (pinfunction "17_17") (pintype "passive"))
      (node (ref "P2") (pin "18") (pinfunction "18_18") (pintype "passive"))
      (node (ref "P2") (pin "22") (pinfunction "22_22") (pintype "passive"))
      (node (ref "P2") (pin "5") (pinfunction "5_5") (pintype "passive"))
      (node (ref "P2") (pin "6") (pinfunction "6_6") (pintype "passive"))
      (node (ref "P4") (pin "10") (pinfunction "LED1-_10") (pintype "passive"))
      (node (ref "P4") (pin "8") (pinfunction "CHSGND_8") (pintype "passive"))
      (node (ref "P5") (pin "A1") (pinfunction "GND_A1") (pintype "bidirectional"))
      (node (ref "P5") (pin "B1") (pinfunction "GND_B1") (pintype "bidirectional"))
      (node (ref "P6") (pin "13") (pinfunction "13_13") (pintype "passive"))
      (node (ref "P6") (pin "14") (pinfunction "14_14") (pintype "passive"))
      (node (ref "P9") (pin "0") (pinfunction "GND_0") (pintype "power_in"))
      (node (ref "P9") (pin "4") (pinfunction "GND_4") (pintype "power_in"))
      (node (ref "R19") (pin "2") (pintype "passive"))
      (node (ref "R22") (pin "2") (pintype "passive"))
      (node (ref "R23") (pin "2") (pintype "passive"))
      (node (ref "R54") (pin "1") (pintype "passive"))
      (node (ref "R58") (pin "1") (pintype "passive"))
      (node (ref "S1") (pin "1") (pinfunction "1_1") (pintype "passive"))
      (node (ref "U1") (pin "0") (pinfunction "GND_0") (pintype "power_in"))
      (node (ref "U1") (pin "1") (pinfunction "GND_1") (pintype "power_in"))
      (node (ref "U3") (pin "10") (pinfunction "VSS_5_10") (pintype "power_in"))
      (node (ref "U3") (pin "19") (pinfunction "VSSA_19") (pintype "power_in"))
      (node (ref "U3") (pin "27") (pinfunction "VSS_4_27") (pintype "power_in"))
      (node (ref "U3") (pin "49") (pinfunction "VSS_1_49") (pintype "power_in"))
      (node (ref "U3") (pin "74") (pinfunction "VSS_2_74") (pintype "power_in"))
      (node (ref "U3") (pin "99") (pinfunction "VSS_3_99") (pintype "power_in"))
      (node (ref "U4") (pin "1") (pinfunction "GND_1") (pintype "passive"))
    )
    (net (code "101") (name "Net-(C1-Pad2)") (class "Default")
      (node (ref "C1") (pin "2") (pinfunction "2_2") (pintype "passive"))
      (node (ref "P4") (pin "4") (pintype "passive"))
    )
    (net (code "102") (name "Net-(C2-Pad2)") (class "Default")
      (node (ref "C2") (pin "2") (pinfunction "2_2") (pintype "passive"))
      (node (ref "P4") (pin "5") (pintype "passive"))
    )
    (net (code "103") (name "Net-(D5-PadK)") (class "Default")
      (node (ref "D5") (pin "K") (pinfunction "K_K") (pintype "passive"))
      (node (ref "R58") (pin "2") (pintype "passive"))
    )
    (net (code "104") (name "Net-(P2-Pad2)") (class "Default")
      (node (ref "P2") (pin "2") (pinfunction "2_2") (pintype "passive"))
      (node (ref "R35") (pin "1") (pintype "passive"))
      (node (ref "R46") (pin "1") (pintype "passive"))
    )
    (net (code "105") (name "Net-(P2-Pad4)") (class "Default")
      (node (ref "P2") (pin "4") (pinfunction "4_4") (pintype "passive"))
      (node (ref "R44") (pin "1") (pintype "passive"))
      (node (ref "R48") (pin "1") (pintype "passive"))
    )
    (net (code "106") (name "Net-(P4-LED1+)") (class "Default")
      (node (ref "P4") (pin "9") (pinfunction "LED1+_9") (pintype "passive"))
      (node (ref "R7") (pin "1") (pintype "passive"))
    )
    (net (code "107") (name "Net-(P4-LED2-)") (class "Default")
      (node (ref "P4") (pin "11") (pinfunction "LED2-_11") (pintype "passive"))
      (node (ref "R9") (pin "1") (pintype "passive"))
    )
    (net (code "108") (name "Net-(P5-CC-PadA5)") (class "Default")
      (node (ref "P5") (pin "A5") (pinfunction "CC_A5") (pintype "bidirectional"))
      (node (ref "R22") (pin "1") (pintype "passive"))
    )
    (net (code "109") (name "Net-(P5-CC-PadB5)") (class "Default")
      (node (ref "P5") (pin "B5") (pinfunction "CC_B5") (pintype "bidirectional"))
      (node (ref "R19") (pin "1") (pintype "passive"))
    )
    (net (code "110") (name "Net-(R24-Pad2)") (class "Default")
      (node (ref "R24") (pin "2") (pintype "passive"))
      (node (ref "S8") (pin "2") (pinfunction "2_2") (pintype "passive"))
    )
    (net (code "111") (name "Net-(S2-COMMON)") (class "Default")
      (node (ref "F1") (pin "2") (pinfunction "2_2") (pintype "passive"))
      (node (ref "S2") (pin "1") (pinfunction "COMMON_1") (pintype "passive"))
    )
    (net (code "112") (name "Net-(U1-AVDDK)") (class "Default")
      (node (ref "C6") (pin "2") (pinfunction "2_2") (pintype "passive"))
      (node (ref "U1") (pin "2") (pinfunction "AVDDK_2") (pintype "power_in"))
    )
    (net (code "113") (name "Net-(U1-DVDDK)") (class "Default")
      (node (ref "C5") (pin "2") (pinfunction "2_2") (pintype "passive"))
      (node (ref "U1") (pin "29") (pinfunction "DVDDK_29") (pintype "power_in"))
    )
    (net (code "114") (name "Net-(U1-RXDV)") (class "Default")
      (node (ref "R26") (pin "2") (pintype "passive"))
      (node (ref "U1") (pin "8") (pinfunction "RXDV_8") (pintype "output"))
    )
    (net (code "115") (name "VCC182") (class "Default")
      (node (ref "C20") (pin "2") (pinfunction "2_2") (pintype "passive"))
      (node (ref "C7") (pin "2") (pinfunction "2_2") (pintype "passive"))
      (node (ref "C8") (pin "2") (pinfunction "2_2") (pintype "passive"))
      (node (ref "C9") (pin "2") (pinfunction "2_2") (pintype "passive"))
      (node (ref "P4") (pin "12") (pinfunction "LED2+_12") (pintype "passive"))
      (node (ref "R12") (pin "1") (pintype "passive"))
      (node (ref "R13") (pin "1") (pintype "passive"))
      (node (ref "R26") (pin "1") (pintype "passive"))
      (node (ref "R29") (pin "2") (pintype "passive"))
      (node (ref "U1") (pin "14") (pinfunction "AVDD33_14") (pintype "power_in"))
      (node (ref "U1") (pin "30") (pinfunction "VDDIO_30") (pintype "power_in"))
      (node (ref "U1") (pin "7") (pinfunction "AVDD33_7") (pintype "power_in"))
    )
    (net (code "116") (name "unconnected-(P4-NC-Pad7)") (class "Default")
      (node (ref "P4") (pin "7") (pinfunction "NC_7") (pintype "passive"))
    )
    (net (code "117") (name "unconnected-(P5-RFU1-PadA8)") (class "Default")
      (node (ref "P5") (pin "A8") (pinfunction "RFU1_A8") (pintype "bidirectional+no_connect"))
    )
    (net (code "118") (name "unconnected-(P5-RFU1-PadB8)") (class "Default")
      (node (ref "P5") (pin "B8") (pinfunction "RFU1_B8") (pintype "bidirectional+no_connect"))
    )
    (net (code "119") (name "unconnected-(S2-NO-Pad3)") (class "Default")
      (node (ref "S2") (pin "3") (pinfunction "NO_3") (pintype "passive"))
    )
    (net (code "120") (name "unconnected-(U1-COL-Pad27)") (class "Default")
      (node (ref "U1") (pin "27") (pinfunction "COL_27") (pintype "output"))
    )
    (net (code "121") (name "unconnected-(U1-RXC-Pad13)") (class "Default")
      (node (ref "U1") (pin "13") (pinfunction "RXC_13") (pintype "output"))
    )
    (net (code "122") (name "unconnected-(U1-RXD[3]-Pad12)") (class "Default")
      (node (ref "U1") (pin "12") (pinfunction "RXD[3]_12") (pintype "output"))
    )
    (net (code "123") (name "unconnected-(U1-RXER-Pad28)") (class "Default")
      (node (ref "U1") (pin "28") (pinfunction "RXER_28") (pintype "output"))
    )
    (net (code "124") (name "unconnected-(U1-TXD[2]-Pad18)") (class "Default")
      (node (ref "U1") (pin "18") (pinfunction "TXD[2]_18") (pintype "input"))
    )
    (net (code "125") (name "unconnected-(U1-TXD[3]-Pad19)") (class "Default")
      (node (ref "U1") (pin "19") (pinfunction "TXD[3]_19") (pintype "input"))
    )
    (net (code "126") (name "unconnected-(U3-NC-Pad73)") (class "Default")
      (node (ref "U3") (pin "73") (pinfunction "NC_73") (pintype "tri_state"))
    )
    (net (code "127") (name "unconnected-(U3-PA0{slash}WKUP{slash}ADC0-Pad23)") (class "Default")
      (node (ref "U3") (pin "23") (pinfunction "PA0/WKUP/ADC0_23") (pintype "bidirectional"))
    )
    (net (code "128") (name "unconnected-(U3-PA3{slash}ADC3-Pad26)") (class "Default")
      (node (ref "U3") (pin "26") (pinfunction "PA3/ADC3_26") (pintype "bidirectional"))
    )
    (net (code "129") (name "unconnected-(U3-PB0{slash}ADC8-Pad35)") (class "Default")
      (node (ref "U3") (pin "35") (pinfunction "PB0/ADC8_35") (pintype "bidirectional"))
    )
    (net (code "130") (name "unconnected-(U3-PB1{slash}ADC9-Pad36)") (class "Default")
      (node (ref "U3") (pin "36") (pinfunction "PB1/ADC9_36") (pintype "bidirectional"))
    )
    (net (code "131") (name "unconnected-(U3-PB8-Pad95)") (class "Default")
      (node (ref "U3") (pin "95") (pinfunction "PB8_95") (pintype "bidirectional"))
    )
    (net (code "132") (name "unconnected-(U3-PB10-Pad47)") (class "Default")
      (node (ref "U3") (pin "47") (pinfunction "PB10_47") (pintype "bidirectional"))
    )
    (net (code "133") (name "unconnected-(U3-PC0{slash}ADC10-Pad15)") (class "Default")
      (node (ref "U3") (pin "15") (pinfunction "PC0/ADC10_15") (pintype "bidirectional"))
    )
    (net (code "134") (name "unconnected-(U3-PC2{slash}ADC12-Pad17)") (class "Default")
      (node (ref "U3") (pin "17") (pinfunction "PC2/ADC12_17") (pintype "bidirectional"))
    )
    (net (code "135") (name "unconnected-(U3-PC3{slash}ADC13-Pad18)") (class "Default")
      (node (ref "U3") (pin "18") (pinfunction "PC3/ADC13_18") (pintype "bidirectional"))
    )
  )
)
